# stm32nes.net
KiCad netlist of a schematic drawn in Altium Designer
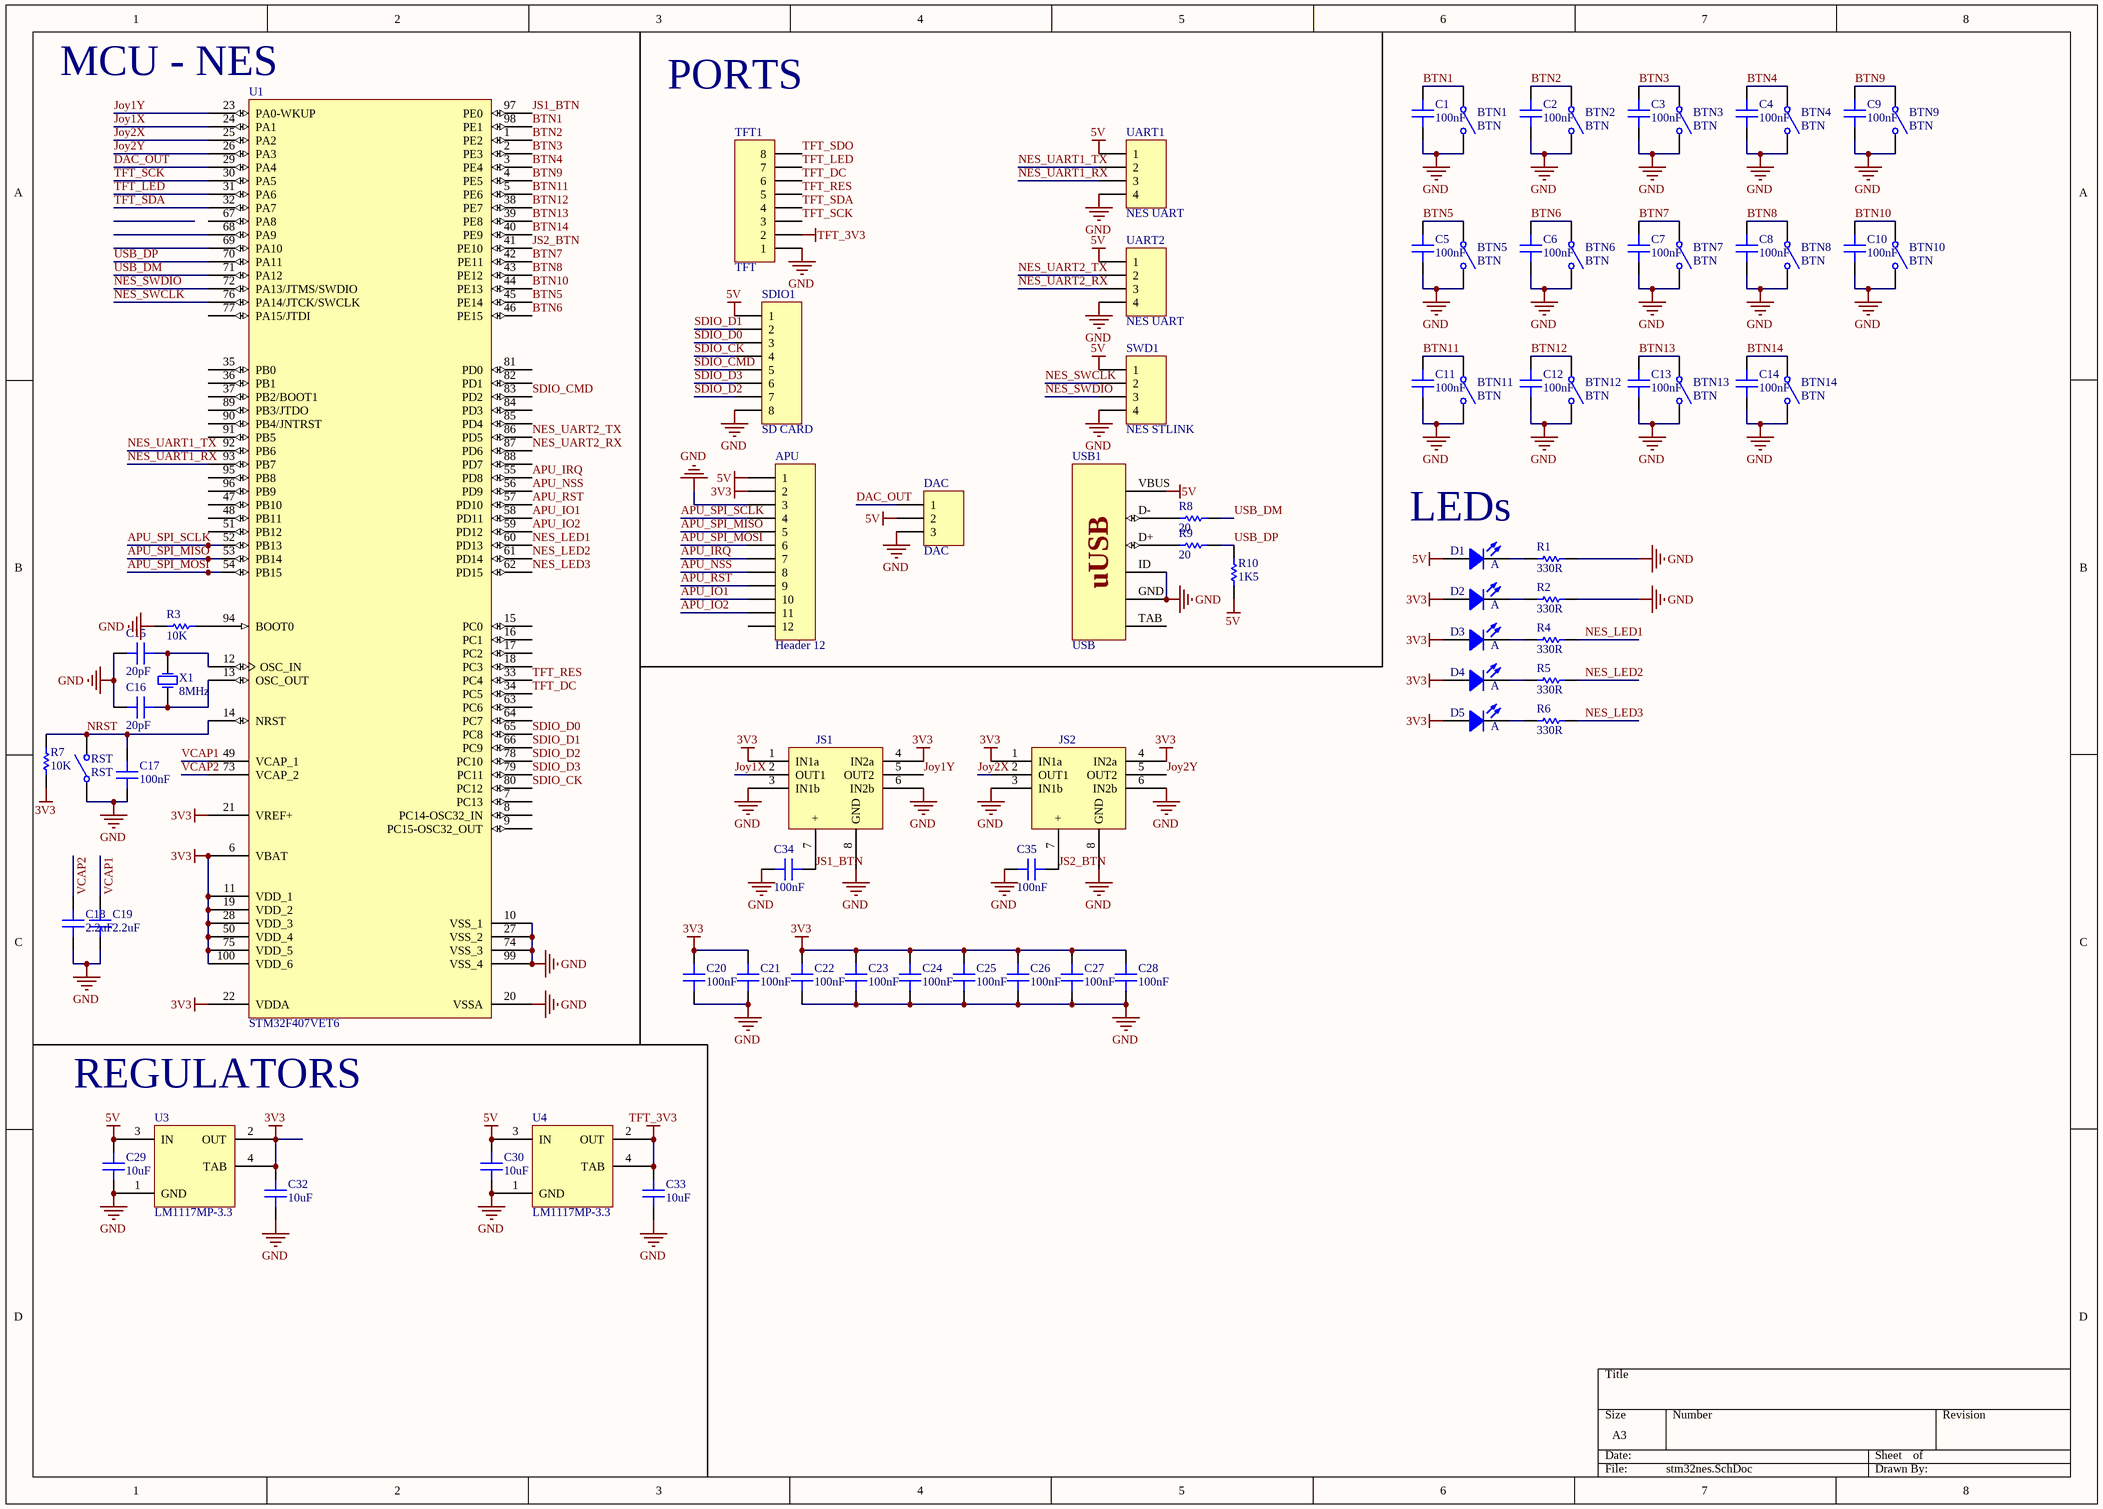
[diagram p0: stm32nes.SchDoc]

(export (version "E")
  (design (tool "Eeschema 10.0.6"))
  (components
    (comp (ref "APU")
      (value "Header 12")
      (footprint "HDR1X12")
      (description "Header, 12-Pin")
      (fields (field (name "PUBLISHER") "Altium Limited"))
      (libsource (lib "Robocn_connectors") (part "Header 12"))
    )
    (comp (ref "BTN1")
      (value "BTN")
      (footprint "switch2:PCBComponent_1")
      (description "Single-Pole, Single-Throw Switch")
      (fields (field (name "PUBLISHER") "Altium Limited"))
      (libsource (lib "Robocn_connectors") (part "SW-SPST"))
    )
    (comp (ref "BTN2")
      (value "BTN")
      (footprint "switch2:PCBComponent_1")
      (description "Single-Pole, Single-Throw Switch")
      (fields (field (name "PUBLISHER") "Altium Limited"))
      (libsource (lib "Robocn_connectors") (part "SW-SPST"))
    )
    (comp (ref "BTN3")
      (value "BTN")
      (footprint "switch2:PCBComponent_1")
      (description "Single-Pole, Single-Throw Switch")
      (fields (field (name "PUBLISHER") "Altium Limited"))
      (libsource (lib "Robocn_connectors") (part "SW-SPST"))
    )
    (comp (ref "BTN4")
      (value "BTN")
      (footprint "switch2:PCBComponent_1")
      (description "Single-Pole, Single-Throw Switch")
      (fields (field (name "PUBLISHER") "Altium Limited"))
      (libsource (lib "Robocn_connectors") (part "SW-SPST"))
    )
    (comp (ref "BTN5")
      (value "BTN")
      (footprint "switch2:PCBComponent_1")
      (description "Single-Pole, Single-Throw Switch")
      (fields (field (name "PUBLISHER") "Altium Limited"))
      (libsource (lib "Robocn_connectors") (part "SW-SPST"))
    )
    (comp (ref "BTN6")
      (value "BTN")
      (footprint "switch2:PCBComponent_1")
      (description "Single-Pole, Single-Throw Switch")
      (fields (field (name "PUBLISHER") "Altium Limited"))
      (libsource (lib "Robocn_connectors") (part "SW-SPST"))
    )
    (comp (ref "BTN7")
      (value "BTN")
      (footprint "switch2:PCBComponent_1")
      (description "Single-Pole, Single-Throw Switch")
      (fields (field (name "PUBLISHER") "Altium Limited"))
      (libsource (lib "Robocn_connectors") (part "SW-SPST"))
    )
    (comp (ref "BTN8")
      (value "BTN")
      (footprint "switch2:PCBComponent_1")
      (description "Single-Pole, Single-Throw Switch")
      (fields (field (name "PUBLISHER") "Altium Limited"))
      (libsource (lib "Robocn_connectors") (part "SW-SPST"))
    )
    (comp (ref "BTN9")
      (value "BTN")
      (footprint "switch2:PCBComponent_1")
      (description "Single-Pole, Single-Throw Switch")
      (fields (field (name "PUBLISHER") "Altium Limited"))
      (libsource (lib "Robocn_connectors") (part "SW-SPST"))
    )
    (comp (ref "BTN10")
      (value "BTN")
      (footprint "switch2:PCBComponent_1")
      (description "Single-Pole, Single-Throw Switch")
      (fields (field (name "PUBLISHER") "Altium Limited"))
      (libsource (lib "Robocn_connectors") (part "SW-SPST"))
    )
    (comp (ref "BTN11")
      (value "BTN")
      (footprint "switch2:PCBComponent_1")
      (description "Single-Pole, Single-Throw Switch")
      (fields (field (name "PUBLISHER") "Altium Limited"))
      (libsource (lib "Robocn_connectors") (part "SW-SPST"))
    )
    (comp (ref "BTN12")
      (value "BTN")
      (footprint "switch2:PCBComponent_1")
      (description "Single-Pole, Single-Throw Switch")
      (fields (field (name "PUBLISHER") "Altium Limited"))
      (libsource (lib "Robocn_connectors") (part "SW-SPST"))
    )
    (comp (ref "BTN13")
      (value "BTN")
      (footprint "switch2:PCBComponent_1")
      (description "Single-Pole, Single-Throw Switch")
      (fields (field (name "PUBLISHER") "Altium Limited"))
      (libsource (lib "Robocn_connectors") (part "SW-SPST"))
    )
    (comp (ref "BTN14")
      (value "BTN")
      (footprint "switch2:PCBComponent_1")
      (description "Single-Pole, Single-Throw Switch")
      (fields (field (name "PUBLISHER") "Altium Limited"))
      (libsource (lib "Robocn_connectors") (part "SW-SPST"))
    )
    (comp (ref "C1")
      (value "100nF")
      (footprint "CC2012-0805")
      (description "Capacitor (Semiconductor SIM Model)")
      (fields (field (name "PUBLISHER") "Altium Limited"))
      (libsource (lib "Robocon_RCL") (part "Cap Semi"))
    )
    (comp (ref "C2")
      (value "100nF")
      (footprint "CC2012-0805")
      (description "Capacitor (Semiconductor SIM Model)")
      (fields (field (name "PUBLISHER") "Altium Limited"))
      (libsource (lib "Robocon_RCL") (part "Cap Semi"))
    )
    (comp (ref "C3")
      (value "100nF")
      (footprint "CC2012-0805")
      (description "Capacitor (Semiconductor SIM Model)")
      (fields (field (name "PUBLISHER") "Altium Limited"))
      (libsource (lib "Robocon_RCL") (part "Cap Semi"))
    )
    (comp (ref "C4")
      (value "100nF")
      (footprint "CC2012-0805")
      (description "Capacitor (Semiconductor SIM Model)")
      (fields (field (name "PUBLISHER") "Altium Limited"))
      (libsource (lib "Robocon_RCL") (part "Cap Semi"))
    )
    (comp (ref "C5")
      (value "100nF")
      (footprint "CC2012-0805")
      (description "Capacitor (Semiconductor SIM Model)")
      (fields (field (name "PUBLISHER") "Altium Limited"))
      (libsource (lib "Robocon_RCL") (part "Cap Semi"))
    )
    (comp (ref "C6")
      (value "100nF")
      (footprint "CC2012-0805")
      (description "Capacitor (Semiconductor SIM Model)")
      (fields (field (name "PUBLISHER") "Altium Limited"))
      (libsource (lib "Robocon_RCL") (part "Cap Semi"))
    )
    (comp (ref "C7")
      (value "100nF")
      (footprint "CC2012-0805")
      (description "Capacitor (Semiconductor SIM Model)")
      (fields (field (name "PUBLISHER") "Altium Limited"))
      (libsource (lib "Robocon_RCL") (part "Cap Semi"))
    )
    (comp (ref "C8")
      (value "100nF")
      (footprint "CC2012-0805")
      (description "Capacitor (Semiconductor SIM Model)")
      (fields (field (name "PUBLISHER") "Altium Limited"))
      (libsource (lib "Robocon_RCL") (part "Cap Semi"))
    )
    (comp (ref "C9")
      (value "100nF")
      (footprint "CC2012-0805")
      (description "Capacitor (Semiconductor SIM Model)")
      (fields (field (name "PUBLISHER") "Altium Limited"))
      (libsource (lib "Robocon_RCL") (part "Cap Semi"))
    )
    (comp (ref "C10")
      (value "100nF")
      (footprint "CC2012-0805")
      (description "Capacitor (Semiconductor SIM Model)")
      (fields (field (name "PUBLISHER") "Altium Limited"))
      (libsource (lib "Robocon_RCL") (part "Cap Semi"))
    )
    (comp (ref "C11")
      (value "100nF")
      (footprint "CC2012-0805")
      (description "Capacitor (Semiconductor SIM Model)")
      (fields (field (name "PUBLISHER") "Altium Limited"))
      (libsource (lib "Robocon_RCL") (part "Cap Semi"))
    )
    (comp (ref "C12")
      (value "100nF")
      (footprint "CC2012-0805")
      (description "Capacitor (Semiconductor SIM Model)")
      (fields (field (name "PUBLISHER") "Altium Limited"))
      (libsource (lib "Robocon_RCL") (part "Cap Semi"))
    )
    (comp (ref "C13")
      (value "100nF")
      (footprint "CC2012-0805")
      (description "Capacitor (Semiconductor SIM Model)")
      (fields (field (name "PUBLISHER") "Altium Limited"))
      (libsource (lib "Robocon_RCL") (part "Cap Semi"))
    )
    (comp (ref "C14")
      (value "100nF")
      (footprint "CC2012-0805")
      (description "Capacitor (Semiconductor SIM Model)")
      (fields (field (name "PUBLISHER") "Altium Limited"))
      (libsource (lib "Robocon_RCL") (part "Cap Semi"))
    )
    (comp (ref "C15")
      (value "20pF")
      (footprint "CC2012-0805")
      (description "Capacitor (Semiconductor SIM Model)")
      (fields (field (name "PUBLISHER") "Altium Limited"))
      (libsource (lib "Robocon_RCL") (part "Cap Semi"))
    )
    (comp (ref "C16")
      (value "20pF")
      (footprint "CC2012-0805")
      (description "Capacitor (Semiconductor SIM Model)")
      (fields (field (name "PUBLISHER") "Altium Limited"))
      (libsource (lib "Robocon_RCL") (part "Cap Semi"))
    )
    (comp (ref "C17")
      (value "100nF")
      (footprint "CC2012-0805")
      (description "Capacitor (Semiconductor SIM Model)")
      (fields (field (name "PUBLISHER") "Altium Limited"))
      (libsource (lib "Robocon_RCL") (part "Cap Semi"))
    )
    (comp (ref "C18")
      (value "2.2uF")
      (footprint "CC2012-0805")
      (description "Capacitor (Semiconductor SIM Model)")
      (fields (field (name "PUBLISHER") "Altium Limited"))
      (libsource (lib "Robocon_RCL") (part "Cap Semi"))
    )
    (comp (ref "C19")
      (value "2.2uF")
      (footprint "CC2012-0805")
      (description "Capacitor (Semiconductor SIM Model)")
      (fields (field (name "PUBLISHER") "Altium Limited"))
      (libsource (lib "Robocon_RCL") (part "Cap Semi"))
    )
    (comp (ref "C20")
      (value "100nF")
      (footprint "CC2012-0805")
      (description "Capacitor (Semiconductor SIM Model)")
      (fields (field (name "PUBLISHER") "Altium Limited"))
      (libsource (lib "Robocon_RCL") (part "Cap Semi"))
    )
    (comp (ref "C21")
      (value "100nF")
      (footprint "CC2012-0805")
      (description "Capacitor (Semiconductor SIM Model)")
      (fields (field (name "PUBLISHER") "Altium Limited"))
      (libsource (lib "Robocon_RCL") (part "Cap Semi"))
    )
    (comp (ref "C22")
      (value "100nF")
      (footprint "CC2012-0805")
      (description "Capacitor (Semiconductor SIM Model)")
      (fields (field (name "PUBLISHER") "Altium Limited"))
      (libsource (lib "Robocon_RCL") (part "Cap Semi"))
    )
    (comp (ref "C23")
      (value "100nF")
      (footprint "CC2012-0805")
      (description "Capacitor (Semiconductor SIM Model)")
      (fields (field (name "PUBLISHER") "Altium Limited"))
      (libsource (lib "Robocon_RCL") (part "Cap Semi"))
    )
    (comp (ref "C24")
      (value "100nF")
      (footprint "CC2012-0805")
      (description "Capacitor (Semiconductor SIM Model)")
      (fields (field (name "PUBLISHER") "Altium Limited"))
      (libsource (lib "Robocon_RCL") (part "Cap Semi"))
    )
    (comp (ref "C25")
      (value "100nF")
      (footprint "CC2012-0805")
      (description "Capacitor (Semiconductor SIM Model)")
      (fields (field (name "PUBLISHER") "Altium Limited"))
      (libsource (lib "Robocon_RCL") (part "Cap Semi"))
    )
    (comp (ref "C26")
      (value "100nF")
      (footprint "CC2012-0805")
      (description "Capacitor (Semiconductor SIM Model)")
      (fields (field (name "PUBLISHER") "Altium Limited"))
      (libsource (lib "Robocon_RCL") (part "Cap Semi"))
    )
    (comp (ref "C27")
      (value "100nF")
      (footprint "CC2012-0805")
      (description "Capacitor (Semiconductor SIM Model)")
      (fields (field (name "PUBLISHER") "Altium Limited"))
      (libsource (lib "Robocon_RCL") (part "Cap Semi"))
    )
    (comp (ref "C28")
      (value "100nF")
      (footprint "CC2012-0805")
      (description "Capacitor (Semiconductor SIM Model)")
      (fields (field (name "PUBLISHER") "Altium Limited"))
      (libsource (lib "Robocon_RCL") (part "Cap Semi"))
    )
    (comp (ref "C29")
      (value "10uF")
      (footprint "CC2012-0805")
      (description "Capacitor (Semiconductor SIM Model)")
      (fields (field (name "PUBLISHER") "Altium Limited"))
      (libsource (lib "Robocon_RCL") (part "Cap Semi"))
    )
    (comp (ref "C30")
      (value "10uF")
      (footprint "CC2012-0805")
      (description "Capacitor (Semiconductor SIM Model)")
      (fields (field (name "PUBLISHER") "Altium Limited"))
      (libsource (lib "Robocon_RCL") (part "Cap Semi"))
    )
    (comp (ref "C32")
      (value "10uF")
      (footprint "CC2012-0805")
      (description "Capacitor (Semiconductor SIM Model)")
      (fields (field (name "PUBLISHER") "Altium Limited"))
      (libsource (lib "Robocon_RCL") (part "Cap Semi"))
    )
    (comp (ref "C33")
      (value "10uF")
      (footprint "CC2012-0805")
      (description "Capacitor (Semiconductor SIM Model)")
      (fields (field (name "PUBLISHER") "Altium Limited"))
      (libsource (lib "Robocon_RCL") (part "Cap Semi"))
    )
    (comp (ref "C34")
      (value "100nF")
      (footprint "CC2012-0805")
      (description "Capacitor (Semiconductor SIM Model)")
      (fields (field (name "PUBLISHER") "Altium Limited"))
      (libsource (lib "Robocon_RCL") (part "Cap Semi"))
    )
    (comp (ref "C35")
      (value "100nF")
      (footprint "CC2012-0805")
      (description "Capacitor (Semiconductor SIM Model)")
      (fields (field (name "PUBLISHER") "Altium Limited"))
      (libsource (lib "Robocon_RCL") (part "Cap Semi"))
    )
    (comp (ref "D1")
      (value "A")
      (footprint "D0805")
      (description "Typical RED GaAs LED")
      (fields (field (name "PUBLISHER") "Altium Limited"))
      (libsource (lib "Robocon_BJT") (part "LED"))
    )
    (comp (ref "D2")
      (value "A")
      (footprint "D0805")
      (description "Typical RED GaAs LED")
      (fields (field (name "PUBLISHER") "Altium Limited"))
      (libsource (lib "Robocon_BJT") (part "LED"))
    )
    (comp (ref "D3")
      (value "A")
      (footprint "D0805")
      (description "Typical RED GaAs LED")
      (fields (field (name "PUBLISHER") "Altium Limited"))
      (libsource (lib "Robocon_BJT") (part "LED"))
    )
    (comp (ref "D4")
      (value "A")
      (footprint "D0805")
      (description "Typical RED GaAs LED")
      (fields (field (name "PUBLISHER") "Altium Limited"))
      (libsource (lib "Robocon_BJT") (part "LED"))
    )
    (comp (ref "D5")
      (value "A")
      (footprint "D0805")
      (description "Typical RED GaAs LED")
      (fields (field (name "PUBLISHER") "Altium Limited"))
      (libsource (lib "Robocon_BJT") (part "LED"))
    )
    (comp (ref "DAC")
      (value "DAC")
      (footprint "LOCKEDHDR-3W")
      (description "Header, 3-Pin")
      (fields (field (name "PUBLISHER") "Altium Limited"))
      (libsource (lib "Robocn_connectors") (part "Header 3"))
    )
    (comp (ref "JS1") (value "Joystick") (footprint "B10K-1") (libsource (lib "Joystick2") (part "B10K-1")))
    (comp (ref "JS2") (value "Joystick") (footprint "B10K-1") (libsource (lib "Joystick2") (part "B10K-1")))
    (comp (ref "R1")
      (value "330R")
      (footprint "CR2012-0805")
      (description "Semiconductor Resistor")
      (fields (field (name "PUBLISHER") "Altium Limited"))
      (libsource (lib "Robocon_RCL") (part "Res Semi"))
    )
    (comp (ref "R2")
      (value "330R")
      (footprint "CR2012-0805")
      (description "Semiconductor Resistor")
      (fields (field (name "PUBLISHER") "Altium Limited"))
      (libsource (lib "Robocon_RCL") (part "Res Semi"))
    )
    (comp (ref "R3")
      (value "10K")
      (footprint "CR2012-0805")
      (description "Semiconductor Resistor")
      (fields (field (name "PUBLISHER") "Altium Limited"))
      (libsource (lib "Robocon_RCL") (part "Res Semi"))
    )
    (comp (ref "R4")
      (value "330R")
      (footprint "CR2012-0805")
      (description "Semiconductor Resistor")
      (fields (field (name "PUBLISHER") "Altium Limited"))
      (libsource (lib "Robocon_RCL") (part "Res Semi"))
    )
    (comp (ref "R5")
      (value "330R")
      (footprint "CR2012-0805")
      (description "Semiconductor Resistor")
      (fields (field (name "PUBLISHER") "Altium Limited"))
      (libsource (lib "Robocon_RCL") (part "Res Semi"))
    )
    (comp (ref "R6")
      (value "330R")
      (footprint "CR2012-0805")
      (description "Semiconductor Resistor")
      (fields (field (name "PUBLISHER") "Altium Limited"))
      (libsource (lib "Robocon_RCL") (part "Res Semi"))
    )
    (comp (ref "R7")
      (value "10K")
      (footprint "CR2012-0805")
      (description "Semiconductor Resistor")
      (fields (field (name "PUBLISHER") "Altium Limited"))
      (libsource (lib "Robocon_RCL") (part "Res Semi"))
    )
    (comp (ref "R8")
      (value "20")
      (footprint "CR2012-0805")
      (description "Semiconductor Resistor")
      (fields (field (name "PUBLISHER") "Altium Limited"))
      (libsource (lib "Robocon_RCL") (part "Res Semi"))
    )
    (comp (ref "R9")
      (value "20")
      (footprint "CR2012-0805")
      (description "Semiconductor Resistor")
      (fields (field (name "PUBLISHER") "Altium Limited"))
      (libsource (lib "Robocon_RCL") (part "Res Semi"))
    )
    (comp (ref "R10")
      (value "1K5")
      (footprint "CR2012-0805")
      (description "Semiconductor Resistor")
      (fields (field (name "PUBLISHER") "Altium Limited"))
      (libsource (lib "Robocon_RCL") (part "Res Semi"))
    )
    (comp (ref "RST")
      (value "RST")
      (footprint "PUSH SWITCH 2-PIN")
      (description "Single-Pole, Single-Throw Switch")
      (fields (field (name "PUBLISHER") "Altium Limited"))
      (libsource (lib "Robocn_connectors") (part "SW-SPST"))
    )
    (comp (ref "SDIO1")
      (value "SD CARD")
      (footprint "HDR1X8")
      (description "Header, 8-Pin")
      (fields (field (name "PUBLISHER") "Altium Limited"))
      (libsource (lib "") (part "Header 8_1"))
    )
    (comp (ref "SWD1")
      (value "NES STLINK")
      (footprint "LOCKEDHDR-4W")
      (description "Header, 4-Pin")
      (fields (field (name "PUBLISHER") "Altium Limited"))
      (libsource (lib "Robocn_connectors") (part "Header 4"))
    )
    (comp (ref "TFT1")
      (value "TFT")
      (footprint "HDR1X8")
      (description "Header, 8-Pin")
      (fields (field (name "PUBLISHER") "Altium Limited"))
      (libsource (lib "Robocn_connectors") (part "Header 8"))
    )
    (comp (ref "U1")
      (value "STM32F407VET6")
      (footprint "LQFP100_N")
      (description "STM32 ARM-based 32-bit MCU with 64 Kbytes Flash, 100-pin LQFP, Industrial Temperature")
      (fields (field (name "PUBLISHER") "Altium Limited"))
      (libsource (lib "Robocon_IC") (part "STM32F407VET6"))
    )
    (comp (ref "U3")
      (value "LM1117MP-3.3")
      (footprint "MP04A_N")
      (description "800mA Low-Dropout Linear Regulator")
      (fields
        (field (name "MANUFACTURER") "National Semiconductor")
        (field (name "DIGIKEYPARTNUMBER") "LM1117MP-3.3CT-ND")
        (field (name "PUBLISHER") "Altium Limited")
      )
      (libsource (lib "Robocon_IC") (part "LM1117MP-3.3"))
    )
    (comp (ref "U4")
      (value "LM1117MP-3.3")
      (footprint "MP04A_N")
      (description "800mA Low-Dropout Linear Regulator")
      (fields
        (field (name "MANUFACTURER") "National Semiconductor")
        (field (name "DIGIKEYPARTNUMBER") "LM1117MP-3.3CT-ND")
        (field (name "PUBLISHER") "Altium Limited")
      )
      (libsource (lib "Robocon_IC") (part "LM1117MP-3.3"))
    )
    (comp (ref "UART1")
      (value "NES UART")
      (footprint "LOCKEDHDR-4W")
      (description "Header, 4-Pin")
      (fields (field (name "PUBLISHER") "Altium Limited"))
      (libsource (lib "Robocn_connectors") (part "Header 4"))
    )
    (comp (ref "UART2")
      (value "NES UART")
      (footprint "LOCKEDHDR-4W")
      (description "Header, 4-Pin")
      (fields (field (name "PUBLISHER") "Altium Limited"))
      (libsource (lib "Robocn_connectors") (part "Header 4"))
    )
    (comp (ref "USB1")
      (value "USB")
      (footprint "USB-UB-S-HM")
      (libsource (lib "Robocn_connectors") (part "USB Series Micro-B"))
    )
    (comp (ref "X1")
      (value "8MHz")
      (footprint "BCY-W2/E4.7")
      (description "Crystal Oscillator")
      (fields (field (name "PUBLISHER") "Altium Limited"))
      (libsource (lib "Robocon_RCL") (part "XTAL"))
    )
  )
  (nets
    (net (code "1") (name "/APU_IO1") (class "Default")
      (node (ref "APU") (pin "10") (pinfunction "10_10") (pintype "passive"))
      (node (ref "U1") (pin "58") (pinfunction "PD11_58") (pintype "bidirectional"))
    )
    (net (code "2") (name "/APU_IO2") (class "Default")
      (node (ref "APU") (pin "11") (pinfunction "11_11") (pintype "passive"))
      (node (ref "U1") (pin "59") (pinfunction "PD12_59") (pintype "bidirectional"))
    )
    (net (code "3") (name "/APU_IRQ") (class "Default")
      (node (ref "APU") (pin "7") (pinfunction "7_7") (pintype "passive"))
      (node (ref "U1") (pin "55") (pinfunction "PD8_55") (pintype "bidirectional"))
    )
    (net (code "4") (name "/APU_NSS") (class "Default")
      (node (ref "APU") (pin "8") (pinfunction "8_8") (pintype "passive"))
      (node (ref "U1") (pin "56") (pinfunction "PD9_56") (pintype "bidirectional"))
    )
    (net (code "5") (name "/APU_RST") (class "Default")
      (node (ref "APU") (pin "9") (pinfunction "9_9") (pintype "passive"))
      (node (ref "U1") (pin "57") (pinfunction "PD10_57") (pintype "bidirectional"))
    )
    (net (code "6") (name "/APU_SPI_MISO") (class "Default")
      (node (ref "APU") (pin "5") (pinfunction "5_5") (pintype "passive"))
      (node (ref "U1") (pin "53") (pinfunction "PB14_53") (pintype "bidirectional"))
    )
    (net (code "7") (name "/APU_SPI_MOSI") (class "Default")
      (node (ref "APU") (pin "6") (pinfunction "6_6") (pintype "passive"))
      (node (ref "U1") (pin "54") (pinfunction "PB15_54") (pintype "bidirectional"))
    )
    (net (code "8") (name "/APU_SPI_SCLK") (class "Default")
      (node (ref "APU") (pin "4") (pinfunction "4_4") (pintype "passive"))
      (node (ref "U1") (pin "52") (pinfunction "PB13_52") (pintype "bidirectional"))
    )
    (net (code "9") (name "/BTN1") (class "Default")
      (node (ref "BTN1") (pin "1") (pinfunction "COMMON_1") (pintype "passive"))
      (node (ref "C1") (pin "1") (pinfunction "1_1") (pintype "passive"))
      (node (ref "U1") (pin "98") (pinfunction "PE1_98") (pintype "bidirectional"))
    )
    (net (code "10") (name "/BTN2") (class "Default")
      (node (ref "BTN2") (pin "1") (pinfunction "COMMON_1") (pintype "passive"))
      (node (ref "C2") (pin "1") (pinfunction "1_1") (pintype "passive"))
      (node (ref "U1") (pin "1") (pinfunction "PE2_1") (pintype "bidirectional"))
    )
    (net (code "11") (name "/BTN3") (class "Default")
      (node (ref "BTN3") (pin "1") (pinfunction "COMMON_1") (pintype "passive"))
      (node (ref "C3") (pin "1") (pinfunction "1_1") (pintype "passive"))
      (node (ref "U1") (pin "2") (pinfunction "PE3_2") (pintype "bidirectional"))
    )
    (net (code "12") (name "/BTN4") (class "Default")
      (node (ref "BTN4") (pin "1") (pinfunction "COMMON_1") (pintype "passive"))
      (node (ref "C4") (pin "1") (pinfunction "1_1") (pintype "passive"))
      (node (ref "U1") (pin "3") (pinfunction "PE4_3") (pintype "bidirectional"))
    )
    (net (code "13") (name "/BTN5") (class "Default")
      (node (ref "BTN5") (pin "1") (pinfunction "COMMON_1") (pintype "passive"))
      (node (ref "C5") (pin "1") (pinfunction "1_1") (pintype "passive"))
      (node (ref "U1") (pin "45") (pinfunction "PE14_45") (pintype "bidirectional"))
    )
    (net (code "14") (name "/BTN6") (class "Default")
      (node (ref "BTN6") (pin "1") (pinfunction "COMMON_1") (pintype "passive"))
      (node (ref "C6") (pin "1") (pinfunction "1_1") (pintype "passive"))
      (node (ref "U1") (pin "46") (pinfunction "PE15_46") (pintype "bidirectional"))
    )
    (net (code "15") (name "/BTN7") (class "Default")
      (node (ref "BTN7") (pin "1") (pinfunction "COMMON_1") (pintype "passive"))
      (node (ref "C7") (pin "1") (pinfunction "1_1") (pintype "passive"))
      (node (ref "U1") (pin "42") (pinfunction "PE11_42") (pintype "bidirectional"))
    )
    (net (code "16") (name "/BTN8") (class "Default")
      (node (ref "BTN8") (pin "1") (pinfunction "COMMON_1") (pintype "passive"))
      (node (ref "C8") (pin "1") (pinfunction "1_1") (pintype "passive"))
      (node (ref "U1") (pin "43") (pinfunction "PE12_43") (pintype "bidirectional"))
    )
    (net (code "17") (name "/BTN9") (class "Default")
      (node (ref "BTN9") (pin "1") (pinfunction "COMMON_1") (pintype "passive"))
      (node (ref "C9") (pin "1") (pinfunction "1_1") (pintype "passive"))
      (node (ref "U1") (pin "4") (pinfunction "PE5_4") (pintype "bidirectional"))
    )
    (net (code "18") (name "/BTN10") (class "Default")
      (node (ref "BTN10") (pin "1") (pinfunction "COMMON_1") (pintype "passive"))
      (node (ref "C10") (pin "1") (pinfunction "1_1") (pintype "passive"))
      (node (ref "U1") (pin "44") (pinfunction "PE13_44") (pintype "bidirectional"))
    )
    (net (code "19") (name "/BTN11") (class "Default")
      (node (ref "BTN11") (pin "1") (pinfunction "COMMON_1") (pintype "passive"))
      (node (ref "C11") (pin "1") (pinfunction "1_1") (pintype "passive"))
      (node (ref "U1") (pin "5") (pinfunction "PE6_5") (pintype "bidirectional"))
    )
    (net (code "20") (name "/BTN12") (class "Default")
      (node (ref "BTN12") (pin "1") (pinfunction "COMMON_1") (pintype "passive"))
      (node (ref "C12") (pin "1") (pinfunction "1_1") (pintype "passive"))
      (node (ref "U1") (pin "38") (pinfunction "PE7_38") (pintype "bidirectional"))
    )
    (net (code "21") (name "/BTN13") (class "Default")
      (node (ref "BTN13") (pin "1") (pinfunction "COMMON_1") (pintype "passive"))
      (node (ref "C13") (pin "1") (pinfunction "1_1") (pintype "passive"))
      (node (ref "U1") (pin "39") (pinfunction "PE8_39") (pintype "bidirectional"))
    )
    (net (code "22") (name "/BTN14") (class "Default")
      (node (ref "BTN14") (pin "1") (pinfunction "COMMON_1") (pintype "passive"))
      (node (ref "C14") (pin "1") (pinfunction "1_1") (pintype "passive"))
      (node (ref "U1") (pin "40") (pinfunction "PE9_40") (pintype "bidirectional"))
    )
    (net (code "23") (name "/DAC_OUT") (class "Default")
      (node (ref "DAC") (pin "1") (pinfunction "1_1") (pintype "passive"))
      (node (ref "U1") (pin "29") (pinfunction "PA4_29") (pintype "bidirectional"))
    )
    (net (code "24") (name "/JS1_BTN") (class "Default")
      (node (ref "C34") (pin "1") (pinfunction "1_1") (pintype "passive"))
      (node (ref "JS1") (pin "7") (pinfunction "+_7") (pintype "passive"))
      (node (ref "U1") (pin "97") (pinfunction "PE0_97") (pintype "bidirectional"))
    )
    (net (code "25") (name "/JS2_BTN") (class "Default")
      (node (ref "C35") (pin "1") (pinfunction "1_1") (pintype "passive"))
      (node (ref "JS2") (pin "7") (pinfunction "+_7") (pintype "passive"))
      (node (ref "U1") (pin "41") (pinfunction "PE10_41") (pintype "bidirectional"))
    )
    (net (code "26") (name "/Joy1X") (class "Default")
      (node (ref "JS1") (pin "2") (pinfunction "OUT1_2") (pintype "passive"))
      (node (ref "U1") (pin "24") (pinfunction "PA1_24") (pintype "bidirectional"))
    )
    (net (code "27") (name "/Joy1Y") (class "Default")
      (node (ref "JS1") (pin "5") (pinfunction "OUT2_5") (pintype "passive"))
      (node (ref "U1") (pin "23") (pinfunction "PA0-WKUP_23") (pintype "bidirectional"))
    )
    (net (code "28") (name "/Joy2X") (class "Default")
      (node (ref "JS2") (pin "2") (pinfunction "OUT1_2") (pintype "passive"))
      (node (ref "U1") (pin "25") (pinfunction "PA2_25") (pintype "bidirectional"))
    )
    (net (code "29") (name "/Joy2Y") (class "Default")
      (node (ref "JS2") (pin "5") (pinfunction "OUT2_5") (pintype "passive"))
      (node (ref "U1") (pin "26") (pinfunction "PA3_26") (pintype "bidirectional"))
    )
    (net (code "30") (name "/NES_LED1") (class "Default")
      (node (ref "R4") (pin "2") (pinfunction "2_2") (pintype "passive"))
      (node (ref "U1") (pin "60") (pinfunction "PD13_60") (pintype "bidirectional"))
    )
    (net (code "31") (name "/NES_LED2") (class "Default")
      (node (ref "R5") (pin "2") (pinfunction "2_2") (pintype "passive"))
      (node (ref "U1") (pin "61") (pinfunction "PD14_61") (pintype "bidirectional"))
    )
    (net (code "32") (name "/NES_LED3") (class "Default")
      (node (ref "R6") (pin "2") (pinfunction "2_2") (pintype "passive"))
      (node (ref "U1") (pin "62") (pinfunction "PD15_62") (pintype "bidirectional"))
    )
    (net (code "33") (name "/NES_SWCLK") (class "Default")
      (node (ref "SWD1") (pin "2") (pinfunction "2_2") (pintype "passive"))
      (node (ref "U1") (pin "76") (pinfunction "PA14/JTCK/SWCLK_76") (pintype "bidirectional"))
    )
    (net (code "34") (name "/NES_SWDIO") (class "Default")
      (node (ref "SWD1") (pin "3") (pinfunction "3_3") (pintype "passive"))
      (node (ref "U1") (pin "72") (pinfunction "PA13/JTMS/SWDIO_72") (pintype "bidirectional"))
    )
    (net (code "35") (name "/NES_UART1_RX") (class "Default")
      (node (ref "U1") (pin "93") (pinfunction "PB7_93") (pintype "bidirectional"))
      (node (ref "UART1") (pin "3") (pinfunction "3_3") (pintype "passive"))
    )
    (net (code "36") (name "/NES_UART1_TX") (class "Default")
      (node (ref "U1") (pin "92") (pinfunction "PB6_92") (pintype "bidirectional"))
      (node (ref "UART1") (pin "2") (pinfunction "2_2") (pintype "passive"))
    )
    (net (code "37") (name "/NES_UART2_RX") (class "Default")
      (node (ref "U1") (pin "87") (pinfunction "PD6_87") (pintype "bidirectional"))
      (node (ref "UART2") (pin "3") (pinfunction "3_3") (pintype "passive"))
    )
    (net (code "38") (name "/NES_UART2_TX") (class "Default")
      (node (ref "U1") (pin "86") (pinfunction "PD5_86") (pintype "bidirectional"))
      (node (ref "UART2") (pin "2") (pinfunction "2_2") (pintype "passive"))
    )
    (net (code "39") (name "/NRST") (class "Default")
      (node (ref "C17") (pin "1") (pinfunction "1_1") (pintype "passive"))
      (node (ref "R7") (pin "2") (pinfunction "2_2") (pintype "passive"))
      (node (ref "RST") (pin "2") (pinfunction "NO_2") (pintype "passive"))
      (node (ref "U1") (pin "14") (pinfunction "NRST_14") (pintype "bidirectional"))
    )
    (net (code "40") (name "/SDIO_CK") (class "Default")
      (node (ref "SDIO1") (pin "4") (pinfunction "4_4") (pintype "passive"))
      (node (ref "U1") (pin "80") (pinfunction "PC12_80") (pintype "bidirectional"))
    )
    (net (code "41") (name "/SDIO_CMD") (class "Default")
      (node (ref "SDIO1") (pin "5") (pinfunction "5_5") (pintype "passive"))
      (node (ref "U1") (pin "83") (pinfunction "PD2_83") (pintype "bidirectional"))
    )
    (net (code "42") (name "/SDIO_D0") (class "Default")
      (node (ref "SDIO1") (pin "3") (pinfunction "3_3") (pintype "passive"))
      (node (ref "U1") (pin "65") (pinfunction "PC8_65") (pintype "bidirectional"))
    )
    (net (code "43") (name "/SDIO_D1") (class "Default")
      (node (ref "SDIO1") (pin "2") (pinfunction "2_2") (pintype "passive"))
      (node (ref "U1") (pin "66") (pinfunction "PC9_66") (pintype "bidirectional"))
    )
    (net (code "44") (name "/SDIO_D2") (class "Default")
      (node (ref "SDIO1") (pin "7") (pinfunction "7_7") (pintype "passive"))
      (node (ref "U1") (pin "78") (pinfunction "PC10_78") (pintype "bidirectional"))
    )
    (net (code "45") (name "/SDIO_D3") (class "Default")
      (node (ref "SDIO1") (pin "6") (pinfunction "6_6") (pintype "passive"))
      (node (ref "U1") (pin "79") (pinfunction "PC11_79") (pintype "bidirectional"))
    )
    (net (code "46") (name "/TFT_DC") (class "Default")
      (node (ref "TFT1") (pin "6") (pinfunction "6_6") (pintype "passive"))
      (node (ref "U1") (pin "34") (pinfunction "PC5_34") (pintype "bidirectional"))
    )
    (net (code "47") (name "/TFT_LED") (class "Default")
      (node (ref "TFT1") (pin "7") (pinfunction "7_7") (pintype "passive"))
      (node (ref "U1") (pin "31") (pinfunction "PA6_31") (pintype "bidirectional"))
    )
    (net (code "48") (name "/TFT_RES") (class "Default")
      (node (ref "TFT1") (pin "5") (pinfunction "5_5") (pintype "passive"))
      (node (ref "U1") (pin "33") (pinfunction "PC4_33") (pintype "bidirectional"))
    )
    (net (code "49") (name "/TFT_SCK") (class "Default")
      (node (ref "TFT1") (pin "3") (pinfunction "3_3") (pintype "passive"))
      (node (ref "U1") (pin "30") (pinfunction "PA5_30") (pintype "bidirectional"))
    )
    (net (code "50") (name "/TFT_SDA") (class "Default")
      (node (ref "TFT1") (pin "4") (pinfunction "4_4") (pintype "passive"))
      (node (ref "U1") (pin "32") (pinfunction "PA7_32") (pintype "bidirectional"))
    )
    (net (code "51") (name "/TFT_SDO") (class "Default")
      (node (ref "TFT1") (pin "8") (pinfunction "8_8") (pintype "passive"))
    )
    (net (code "52") (name "/USB_DM") (class "Default")
      (node (ref "R8") (pin "2") (pinfunction "2_2") (pintype "passive"))
      (node (ref "U1") (pin "71") (pinfunction "PA12_71") (pintype "bidirectional"))
    )
    (net (code "53") (name "/USB_DP") (class "Default")
      (node (ref "R10") (pin "1") (pinfunction "1_1") (pintype "passive"))
      (node (ref "R9") (pin "2") (pinfunction "2_2") (pintype "passive"))
      (node (ref "U1") (pin "70") (pinfunction "PA11_70") (pintype "bidirectional"))
    )
    (net (code "54") (name "/VCAP1") (class "Default")
      (node (ref "C19") (pin "2") (pinfunction "2_2") (pintype "passive"))
      (node (ref "U1") (pin "49") (pinfunction "VCAP_1_49") (pintype "power_in"))
    )
    (net (code "55") (name "/VCAP2") (class "Default")
      (node (ref "C18") (pin "2") (pinfunction "2_2") (pintype "passive"))
      (node (ref "U1") (pin "73") (pinfunction "VCAP_2_73") (pintype "passive"))
    )
    (net (code "56") (name "3V3") (class "Default")
      (node (ref "APU") (pin "2") (pinfunction "2_2") (pintype "passive"))
      (node (ref "C20") (pin "2") (pinfunction "2_2") (pintype "passive"))
      (node (ref "C21") (pin "2") (pinfunction "2_2") (pintype "passive"))
      (node (ref "C22") (pin "2") (pinfunction "2_2") (pintype "passive"))
      (node (ref "C23") (pin "2") (pinfunction "2_2") (pintype "passive"))
      (node (ref "C24") (pin "2") (pinfunction "2_2") (pintype "passive"))
      (node (ref "C25") (pin "2") (pinfunction "2_2") (pintype "passive"))
      (node (ref "C26") (pin "2") (pinfunction "2_2") (pintype "passive"))
      (node (ref "C27") (pin "2") (pinfunction "2_2") (pintype "passive"))
      (node (ref "C28") (pin "2") (pinfunction "2_2") (pintype "passive"))
      (node (ref "C32") (pin "2") (pinfunction "2_2") (pintype "passive"))
      (node (ref "D2") (pin "1") (pinfunction "A_1") (pintype "passive"))
      (node (ref "D3") (pin "1") (pinfunction "A_1") (pintype "passive"))
      (node (ref "D4") (pin "1") (pinfunction "A_1") (pintype "passive"))
      (node (ref "D5") (pin "1") (pinfunction "A_1") (pintype "passive"))
      (node (ref "JS1") (pin "1") (pinfunction "IN1a_1") (pintype "passive"))
      (node (ref "JS1") (pin "4") (pinfunction "IN2a_4") (pintype "passive"))
      (node (ref "JS2") (pin "1") (pinfunction "IN1a_1") (pintype "passive"))
      (node (ref "JS2") (pin "4") (pinfunction "IN2a_4") (pintype "passive"))
      (node (ref "R7") (pin "1") (pinfunction "1_1") (pintype "passive"))
      (node (ref "U1") (pin "100") (pinfunction "VDD_6_100") (pintype "power_in"))
      (node (ref "U1") (pin "11") (pinfunction "VDD_1_11") (pintype "power_in"))
      (node (ref "U1") (pin "19") (pinfunction "VDD_2_19") (pintype "power_in"))
      (node (ref "U1") (pin "21") (pinfunction "VREF+_21") (pintype "power_in"))
      (node (ref "U1") (pin "22") (pinfunction "VDDA_22") (pintype "power_in"))
      (node (ref "U1") (pin "28") (pinfunction "VDD_3_28") (pintype "power_in"))
      (node (ref "U1") (pin "50") (pinfunction "VDD_4_50") (pintype "power_in"))
      (node (ref "U1") (pin "6") (pinfunction "VBAT_6") (pintype "power_in"))
      (node (ref "U1") (pin "75") (pinfunction "VDD_5_75") (pintype "power_in"))
      (node (ref "U3") (pin "2") (pinfunction "OUT_2") (pintype "power_in"))
      (node (ref "U3") (pin "4") (pinfunction "TAB_4") (pintype "power_in"))
    )
    (net (code "57") (name "5V") (class "Default")
      (node (ref "APU") (pin "1") (pinfunction "1_1") (pintype "passive"))
      (node (ref "C29") (pin "2") (pinfunction "2_2") (pintype "passive"))
      (node (ref "C30") (pin "2") (pinfunction "2_2") (pintype "passive"))
      (node (ref "D1") (pin "1") (pinfunction "A_1") (pintype "passive"))
      (node (ref "DAC") (pin "2") (pinfunction "2_2") (pintype "passive"))
      (node (ref "R10") (pin "2") (pinfunction "2_2") (pintype "passive"))
      (node (ref "SDIO1") (pin "1") (pinfunction "1_1") (pintype "passive"))
      (node (ref "SWD1") (pin "1") (pinfunction "1_1") (pintype "passive"))
      (node (ref "U3") (pin "3") (pinfunction "IN_3") (pintype "power_in"))
      (node (ref "U4") (pin "3") (pinfunction "IN_3") (pintype "power_in"))
      (node (ref "UART1") (pin "1") (pinfunction "1_1") (pintype "passive"))
      (node (ref "UART2") (pin "1") (pinfunction "1_1") (pintype "passive"))
      (node (ref "USB1") (pin "VBUS") (pintype "power_in"))
    )
    (net (code "58") (name "GND") (class "Default")
      (node (ref "APU") (pin "3") (pinfunction "3_3") (pintype "passive"))
      (node (ref "BTN1") (pin "2") (pinfunction "NO_2") (pintype "passive"))
      (node (ref "BTN10") (pin "2") (pinfunction "NO_2") (pintype "passive"))
      (node (ref "BTN11") (pin "2") (pinfunction "NO_2") (pintype "passive"))
      (node (ref "BTN12") (pin "2") (pinfunction "NO_2") (pintype "passive"))
      (node (ref "BTN13") (pin "2") (pinfunction "NO_2") (pintype "passive"))
      (node (ref "BTN14") (pin "2") (pinfunction "NO_2") (pintype "passive"))
      (node (ref "BTN2") (pin "2") (pinfunction "NO_2") (pintype "passive"))
      (node (ref "BTN3") (pin "2") (pinfunction "NO_2") (pintype "passive"))
      (node (ref "BTN4") (pin "2") (pinfunction "NO_2") (pintype "passive"))
      (node (ref "BTN5") (pin "2") (pinfunction "NO_2") (pintype "passive"))
      (node (ref "BTN6") (pin "2") (pinfunction "NO_2") (pintype "passive"))
      (node (ref "BTN7") (pin "2") (pinfunction "NO_2") (pintype "passive"))
      (node (ref "BTN8") (pin "2") (pinfunction "NO_2") (pintype "passive"))
      (node (ref "BTN9") (pin "2") (pinfunction "NO_2") (pintype "passive"))
      (node (ref "C1") (pin "2") (pinfunction "2_2") (pintype "passive"))
      (node (ref "C10") (pin "2") (pinfunction "2_2") (pintype "passive"))
      (node (ref "C11") (pin "2") (pinfunction "2_2") (pintype "passive"))
      (node (ref "C12") (pin "2") (pinfunction "2_2") (pintype "passive"))
      (node (ref "C13") (pin "2") (pinfunction "2_2") (pintype "passive"))
      (node (ref "C14") (pin "2") (pinfunction "2_2") (pintype "passive"))
      (node (ref "C15") (pin "2") (pinfunction "2_2") (pintype "passive"))
      (node (ref "C16") (pin "2") (pinfunction "2_2") (pintype "passive"))
      (node (ref "C17") (pin "2") (pinfunction "2_2") (pintype "passive"))
      (node (ref "C18") (pin "1") (pinfunction "1_1") (pintype "passive"))
      (node (ref "C19") (pin "1") (pinfunction "1_1") (pintype "passive"))
      (node (ref "C2") (pin "2") (pinfunction "2_2") (pintype "passive"))
      (node (ref "C20") (pin "1") (pinfunction "1_1") (pintype "passive"))
      (node (ref "C21") (pin "1") (pinfunction "1_1") (pintype "passive"))
      (node (ref "C22") (pin "1") (pinfunction "1_1") (pintype "passive"))
      (node (ref "C23") (pin "1") (pinfunction "1_1") (pintype "passive"))
      (node (ref "C24") (pin "1") (pinfunction "1_1") (pintype "passive"))
      (node (ref "C25") (pin "1") (pinfunction "1_1") (pintype "passive"))
      (node (ref "C26") (pin "1") (pinfunction "1_1") (pintype "passive"))
      (node (ref "C27") (pin "1") (pinfunction "1_1") (pintype "passive"))
      (node (ref "C28") (pin "1") (pinfunction "1_1") (pintype "passive"))
      (node (ref "C29") (pin "1") (pinfunction "1_1") (pintype "passive"))
      (node (ref "C3") (pin "2") (pinfunction "2_2") (pintype "passive"))
      (node (ref "C30") (pin "1") (pinfunction "1_1") (pintype "passive"))
      (node (ref "C32") (pin "1") (pinfunction "1_1") (pintype "passive"))
      (node (ref "C33") (pin "1") (pinfunction "1_1") (pintype "passive"))
      (node (ref "C34") (pin "2") (pinfunction "2_2") (pintype "passive"))
      (node (ref "C35") (pin "2") (pinfunction "2_2") (pintype "passive"))
      (node (ref "C4") (pin "2") (pinfunction "2_2") (pintype "passive"))
      (node (ref "C5") (pin "2") (pinfunction "2_2") (pintype "passive"))
      (node (ref "C6") (pin "2") (pinfunction "2_2") (pintype "passive"))
      (node (ref "C7") (pin "2") (pinfunction "2_2") (pintype "passive"))
      (node (ref "C8") (pin "2") (pinfunction "2_2") (pintype "passive"))
      (node (ref "C9") (pin "2") (pinfunction "2_2") (pintype "passive"))
      (node (ref "DAC") (pin "3") (pinfunction "3_3") (pintype "passive"))
      (node (ref "JS1") (pin "3") (pinfunction "IN1b_3") (pintype "passive"))
      (node (ref "JS1") (pin "6") (pinfunction "IN2b_6") (pintype "passive"))
      (node (ref "JS1") (pin "8") (pinfunction "GND_8") (pintype "passive"))
      (node (ref "JS2") (pin "3") (pinfunction "IN1b_3") (pintype "passive"))
      (node (ref "JS2") (pin "6") (pinfunction "IN2b_6") (pintype "passive"))
      (node (ref "JS2") (pin "8") (pinfunction "GND_8") (pintype "passive"))
      (node (ref "R1") (pin "2") (pinfunction "2_2") (pintype "passive"))
      (node (ref "R2") (pin "2") (pinfunction "2_2") (pintype "passive"))
      (node (ref "R3") (pin "1") (pinfunction "1_1") (pintype "passive"))
      (node (ref "RST") (pin "1") (pinfunction "COMMON_1") (pintype "passive"))
      (node (ref "SDIO1") (pin "8") (pinfunction "8_8") (pintype "passive"))
      (node (ref "SWD1") (pin "4") (pinfunction "4_4") (pintype "passive"))
      (node (ref "TFT1") (pin "1") (pinfunction "1_1") (pintype "passive"))
      (node (ref "U1") (pin "10") (pinfunction "VSS_1_10") (pintype "power_in"))
      (node (ref "U1") (pin "20") (pinfunction "VSSA_20") (pintype "power_in"))
      (node (ref "U1") (pin "27") (pinfunction "VSS_2_27") (pintype "power_in"))
      (node (ref "U1") (pin "74") (pinfunction "VSS_3_74") (pintype "power_in"))
      (node (ref "U1") (pin "99") (pinfunction "VSS_4_99") (pintype "power_in"))
      (node (ref "U3") (pin "1") (pinfunction "GND_1") (pintype "power_in"))
      (node (ref "U4") (pin "1") (pinfunction "GND_1") (pintype "power_in"))
      (node (ref "UART1") (pin "4") (pinfunction "4_4") (pintype "passive"))
      (node (ref "UART2") (pin "4") (pinfunction "4_4") (pintype "passive"))
      (node (ref "USB1") (pin "GND") (pintype "power_in"))
      (node (ref "USB1") (pin "ID") (pintype "passive"))
    )
    (net (code "59") (name "Net-(D1-K)") (class "Default")
      (node (ref "D1") (pin "2") (pinfunction "K_2") (pintype "passive"))
      (node (ref "R1") (pin "1") (pinfunction "1_1") (pintype "passive"))
    )
    (net (code "60") (name "Net-(D2-K)") (class "Default")
      (node (ref "D2") (pin "2") (pinfunction "K_2") (pintype "passive"))
      (node (ref "R2") (pin "1") (pinfunction "1_1") (pintype "passive"))
    )
    (net (code "61") (name "Net-(D3-K)") (class "Default")
      (node (ref "D3") (pin "2") (pinfunction "K_2") (pintype "passive"))
      (node (ref "R4") (pin "1") (pinfunction "1_1") (pintype "passive"))
    )
    (net (code "62") (name "Net-(D4-K)") (class "Default")
      (node (ref "D4") (pin "2") (pinfunction "K_2") (pintype "passive"))
      (node (ref "R5") (pin "1") (pinfunction "1_1") (pintype "passive"))
    )
    (net (code "63") (name "Net-(D5-K)") (class "Default")
      (node (ref "D5") (pin "2") (pinfunction "K_2") (pintype "passive"))
      (node (ref "R6") (pin "1") (pinfunction "1_1") (pintype "passive"))
    )
    (net (code "64") (name "Net-(R8-Pad1)") (class "Default")
      (node (ref "R8") (pin "1") (pinfunction "1_1") (pintype "passive"))
      (node (ref "USB1") (pin "D-") (pintype "bidirectional"))
    )
    (net (code "65") (name "Net-(R9-Pad1)") (class "Default")
      (node (ref "R9") (pin "1") (pinfunction "1_1") (pintype "passive"))
      (node (ref "USB1") (pin "D+") (pintype "bidirectional"))
    )
    (net (code "66") (name "Net-(U1-BOOT0)") (class "Default")
      (node (ref "R3") (pin "2") (pinfunction "2_2") (pintype "passive"))
      (node (ref "U1") (pin "94") (pinfunction "BOOT0_94") (pintype "input"))
    )
    (net (code "67") (name "Net-(U1-OSC_IN)") (class "Default")
      (node (ref "C15") (pin "1") (pinfunction "1_1") (pintype "passive"))
      (node (ref "U1") (pin "12") (pinfunction "OSC_IN_12") (pintype "bidirectional"))
      (node (ref "X1") (pin "2") (pinfunction "OSC2_2") (pintype "passive"))
    )
    (net (code "68") (name "Net-(U1-OSC_OUT)") (class "Default")
      (node (ref "C16") (pin "1") (pinfunction "1_1") (pintype "passive"))
      (node (ref "U1") (pin "13") (pinfunction "OSC_OUT_13") (pintype "bidirectional"))
      (node (ref "X1") (pin "1") (pinfunction "OSC1_1") (pintype "passive"))
    )
    (net (code "69") (name "TFT_3V3") (class "Default")
      (node (ref "C33") (pin "2") (pinfunction "2_2") (pintype "passive"))
      (node (ref "TFT1") (pin "2") (pinfunction "2_2") (pintype "passive"))
      (node (ref "U4") (pin "2") (pinfunction "OUT_2") (pintype "power_in"))
      (node (ref "U4") (pin "4") (pinfunction "TAB_4") (pintype "power_in"))
    )
    (net (code "70") (name "unconnected-(APU-Pad12)") (class "Default")
      (node (ref "APU") (pin "12") (pinfunction "12_12") (pintype "passive"))
    )
    (net (code "71") (name "unconnected-(U1-PA8-Pad67)") (class "Default")
      (node (ref "U1") (pin "67") (pinfunction "PA8_67") (pintype "bidirectional"))
    )
    (net (code "72") (name "unconnected-(U1-PA9-Pad68)") (class "Default")
      (node (ref "U1") (pin "68") (pinfunction "PA9_68") (pintype "bidirectional"))
    )
    (net (code "73") (name "unconnected-(U1-PA10-Pad69)") (class "Default")
      (node (ref "U1") (pin "69") (pinfunction "PA10_69") (pintype "bidirectional"))
    )
    (net (code "74") (name "unconnected-(U1-PA15{slash}JTDI-Pad77)") (class "Default")
      (node (ref "U1") (pin "77") (pinfunction "PA15/JTDI_77") (pintype "bidirectional"))
    )
    (net (code "75") (name "unconnected-(U1-PB0-Pad35)") (class "Default")
      (node (ref "U1") (pin "35") (pinfunction "PB0_35") (pintype "bidirectional"))
    )
    (net (code "76") (name "unconnected-(U1-PB1-Pad36)") (class "Default")
      (node (ref "U1") (pin "36") (pinfunction "PB1_36") (pintype "bidirectional"))
    )
    (net (code "77") (name "unconnected-(U1-PB2{slash}BOOT1-Pad37)") (class "Default")
      (node (ref "U1") (pin "37") (pinfunction "PB2/BOOT1_37") (pintype "bidirectional"))
    )
    (net (code "78") (name "unconnected-(U1-PB3{slash}JTDO-Pad89)") (class "Default")
      (node (ref "U1") (pin "89") (pinfunction "PB3/JTDO_89") (pintype "bidirectional"))
    )
    (net (code "79") (name "unconnected-(U1-PB4{slash}JNTRST-Pad90)") (class "Default")
      (node (ref "U1") (pin "90") (pinfunction "PB4/JNTRST_90") (pintype "bidirectional"))
    )
    (net (code "80") (name "unconnected-(U1-PB5-Pad91)") (class "Default")
      (node (ref "U1") (pin "91") (pinfunction "PB5_91") (pintype "bidirectional"))
    )
    (net (code "81") (name "unconnected-(U1-PB8-Pad95)") (class "Default")
      (node (ref "U1") (pin "95") (pinfunction "PB8_95") (pintype "bidirectional"))
    )
    (net (code "82") (name "unconnected-(U1-PB9-Pad96)") (class "Default")
      (node (ref "U1") (pin "96") (pinfunction "PB9_96") (pintype "bidirectional"))
    )
    (net (code "83") (name "unconnected-(U1-PB10-Pad47)") (class "Default")
      (node (ref "U1") (pin "47") (pinfunction "PB10_47") (pintype "bidirectional"))
    )
    (net (code "84") (name "unconnected-(U1-PB11-Pad48)") (class "Default")
      (node (ref "U1") (pin "48") (pinfunction "PB11_48") (pintype "bidirectional"))
    )
    (net (code "85") (name "unconnected-(U1-PB12-Pad51)") (class "Default")
      (node (ref "U1") (pin "51") (pinfunction "PB12_51") (pintype "bidirectional"))
    )
    (net (code "86") (name "unconnected-(U1-PC0-Pad15)") (class "Default")
      (node (ref "U1") (pin "15") (pinfunction "PC0_15") (pintype "bidirectional"))
    )
    (net (code "87") (name "unconnected-(U1-PC1-Pad16)") (class "Default")
      (node (ref "U1") (pin "16") (pinfunction "PC1_16") (pintype "bidirectional"))
    )
    (net (code "88") (name "unconnected-(U1-PC2-Pad17)") (class "Default")
      (node (ref "U1") (pin "17") (pinfunction "PC2_17") (pintype "bidirectional"))
    )
    (net (code "89") (name "unconnected-(U1-PC3-Pad18)") (class "Default")
      (node (ref "U1") (pin "18") (pinfunction "PC3_18") (pintype "bidirectional"))
    )
    (net (code "90") (name "unconnected-(U1-PC6-Pad63)") (class "Default")
      (node (ref "U1") (pin "63") (pinfunction "PC6_63") (pintype "bidirectional"))
    )
    (net (code "91") (name "unconnected-(U1-PC7-Pad64)") (class "Default")
      (node (ref "U1") (pin "64") (pinfunction "PC7_64") (pintype "bidirectional"))
    )
    (net (code "92") (name "unconnected-(U1-PC13-Pad7)") (class "Default")
      (node (ref "U1") (pin "7") (pinfunction "PC13_7") (pintype "bidirectional"))
    )
    (net (code "93") (name "unconnected-(U1-PC14-OSC32_IN-Pad8)") (class "Default")
      (node (ref "U1") (pin "8") (pinfunction "PC14-OSC32_IN_8") (pintype "bidirectional"))
    )
    (net (code "94") (name "unconnected-(U1-PC15-OSC32_OUT-Pad9)") (class "Default")
      (node (ref "U1") (pin "9") (pinfunction "PC15-OSC32_OUT_9") (pintype "bidirectional"))
    )
    (net (code "95") (name "unconnected-(U1-PD0-Pad81)") (class "Default")
      (node (ref "U1") (pin "81") (pinfunction "PD0_81") (pintype "bidirectional"))
    )
    (net (code "96") (name "unconnected-(U1-PD1-Pad82)") (class "Default")
      (node (ref "U1") (pin "82") (pinfunction "PD1_82") (pintype "bidirectional"))
    )
    (net (code "97") (name "unconnected-(U1-PD3-Pad84)") (class "Default")
      (node (ref "U1") (pin "84") (pinfunction "PD3_84") (pintype "bidirectional"))
    )
    (net (code "98") (name "unconnected-(U1-PD4-Pad85)") (class "Default")
      (node (ref "U1") (pin "85") (pinfunction "PD4_85") (pintype "bidirectional"))
    )
    (net (code "99") (name "unconnected-(U1-PD7-Pad88)") (class "Default")
      (node (ref "U1") (pin "88") (pinfunction "PD7_88") (pintype "bidirectional"))
    )
    (net (code "100") (name "unconnected-(USB1-PadTAB)") (class "Default")
      (node (ref "USB1") (pin "TAB") (pintype "power_in"))
    )
  )
)
